# CAN-to-CAN.net
KiCad netlist of a schematic drawn in Altium Designer
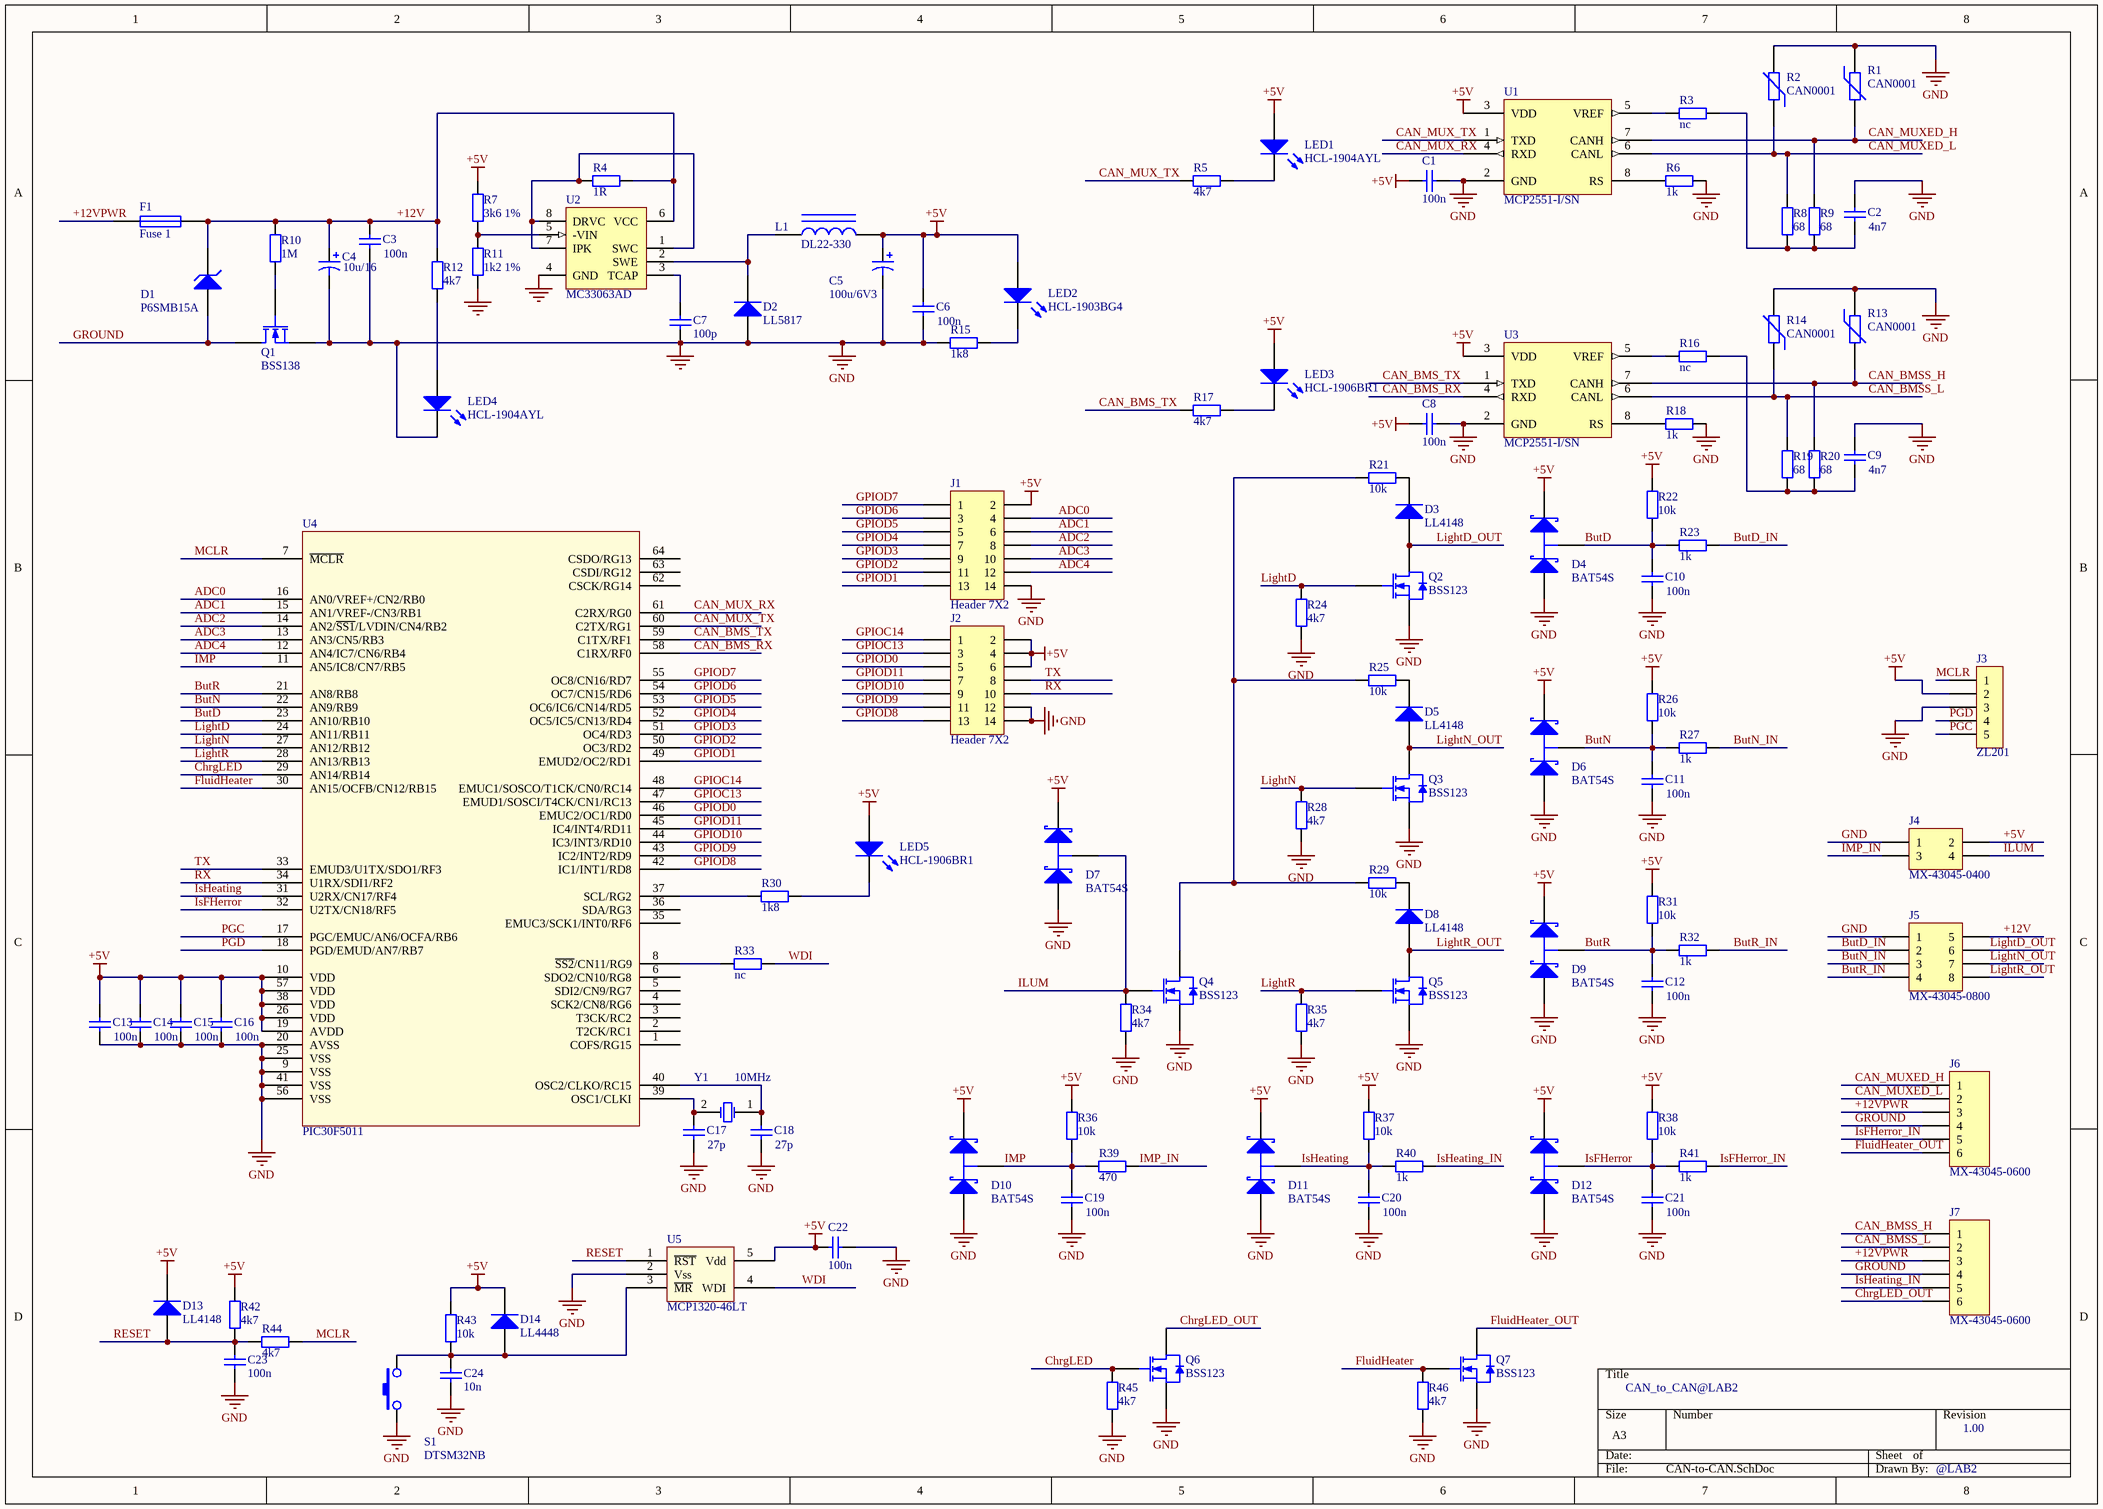
[diagram p0: CAN-to-CAN.SchDoc]

(export (version "E")
  (design (tool "Eeschema 10.0.6"))
  (components
    (comp (ref "C1")
      (value "100n")
      (footprint "0603")
      (description "Capacitor")
      (libsource (lib "Miscellaneous Devices") (part "Cap"))
    )
    (comp (ref "C2")
      (value "4n7")
      (footprint "0603")
      (description "Capacitor")
      (libsource (lib "Miscellaneous Devices") (part "Cap"))
    )
    (comp (ref "C3")
      (value "100n")
      (footprint "3.2X1.6X1.1")
      (description "Capacitor")
      (libsource (lib "Miscellaneous Devices") (part "Cap"))
    )
    (comp (ref "C4")
      (value "10u/16")
      (footprint "1608[0603]")
      (description "Polarized Capacitor (Radial)")
      (libsource (lib "Miscellaneous Devices") (part "Cap Pol1"))
    )
    (comp (ref "C5")
      (value "100u/6V3")
      (footprint "0402")
      (description "Polarized Capacitor (Radial)")
      (libsource (lib "Miscellaneous Devices") (part "Cap Pol1"))
    )
    (comp (ref "C6")
      (value "100n")
      (footprint "0603")
      (description "Capacitor")
      (libsource (lib "Miscellaneous Devices") (part "Cap"))
    )
    (comp (ref "C7")
      (value "100p")
      (footprint "0603")
      (description "Capacitor")
      (libsource (lib "Miscellaneous Devices") (part "Cap"))
    )
    (comp (ref "C8")
      (value "100n")
      (footprint "0603")
      (description "Capacitor")
      (libsource (lib "Miscellaneous Devices") (part "Cap"))
    )
    (comp (ref "C9")
      (value "4n7")
      (footprint "0603")
      (description "Capacitor")
      (libsource (lib "Miscellaneous Devices") (part "Cap"))
    )
    (comp (ref "C10")
      (value "100n")
      (footprint "0603")
      (description "Capacitor")
      (libsource (lib "Miscellaneous Devices") (part "Cap"))
    )
    (comp (ref "C11")
      (value "100n")
      (footprint "0603")
      (description "Capacitor")
      (libsource (lib "Miscellaneous Devices") (part "Cap"))
    )
    (comp (ref "C12")
      (value "100n")
      (footprint "0603")
      (description "Capacitor")
      (libsource (lib "Miscellaneous Devices") (part "Cap"))
    )
    (comp (ref "C13")
      (value "100n")
      (footprint "0603")
      (description "Capacitor")
      (libsource (lib "Miscellaneous Devices") (part "Cap"))
    )
    (comp (ref "C14")
      (value "100n")
      (footprint "0603")
      (description "Capacitor")
      (libsource (lib "Miscellaneous Devices") (part "Cap"))
    )
    (comp (ref "C15")
      (value "100n")
      (footprint "0603")
      (description "Capacitor")
      (libsource (lib "Miscellaneous Devices") (part "Cap"))
    )
    (comp (ref "C16")
      (value "100n")
      (footprint "0603")
      (description "Capacitor")
      (libsource (lib "Miscellaneous Devices") (part "Cap"))
    )
    (comp (ref "C17")
      (value "27p")
      (footprint "0603")
      (description "Capacitor")
      (libsource (lib "Miscellaneous Devices") (part "Cap"))
    )
    (comp (ref "C18")
      (value "27p")
      (footprint "0603")
      (description "Capacitor")
      (libsource (lib "Miscellaneous Devices") (part "Cap"))
    )
    (comp (ref "C19")
      (value "100n")
      (footprint "0603")
      (description "Capacitor")
      (libsource (lib "Miscellaneous Devices") (part "Cap"))
    )
    (comp (ref "C20")
      (value "100n")
      (footprint "0603")
      (description "Capacitor")
      (libsource (lib "Miscellaneous Devices") (part "Cap"))
    )
    (comp (ref "C21")
      (value "100n")
      (footprint "0603")
      (description "Capacitor")
      (libsource (lib "Miscellaneous Devices") (part "Cap"))
    )
    (comp (ref "C22")
      (value "100n")
      (footprint "0603")
      (description "Capacitor")
      (libsource (lib "Miscellaneous Devices") (part "Cap"))
    )
    (comp (ref "C23")
      (value "100n")
      (footprint "0603")
      (description "Capacitor")
      (libsource (lib "Miscellaneous Devices") (part "Cap"))
    )
    (comp (ref "C24")
      (value "10n")
      (footprint "0603")
      (description "Capacitor")
      (libsource (lib "Miscellaneous Devices") (part "Cap"))
    )
    (comp (ref "D1")
      (value "P6SMB15A")
      (footprint "SMB")
      (description "Zener Diode")
      (libsource (lib "Miscellaneous Devices") (part "D Zener"))
    )
    (comp (ref "D2")
      (value "LL5817")
      (footprint "3.2X1.6X1.1")
      (description "High Conductance Fast Diode")
      (libsource (lib "FSC Discrete Diode") (part "1N4148"))
    )
    (comp (ref "D3")
      (value "LL4148")
      (footprint "3.2X1.6X1.1")
      (description "High Conductance Fast Diode")
      (libsource (lib "FSC Discrete Diode") (part "1N4148"))
    )
    (comp (ref "D4")
      (value "BAT54S")
      (footprint "3.2X1.6X1.1")
      (description "Schottky Barrier Double Diode")
      (libsource (lib "Philips Discrete Diode - Schottky") (part "BAT54S"))
    )
    (comp (ref "D5")
      (value "LL4148")
      (footprint "3.2X1.6X1.1")
      (description "High Conductance Fast Diode")
      (libsource (lib "FSC Discrete Diode") (part "1N4148"))
    )
    (comp (ref "D6")
      (value "BAT54S")
      (footprint "3.5X2.8X1.9")
      (description "Schottky Barrier Double Diode")
      (libsource (lib "Philips Discrete Diode - Schottky") (part "BAT54S"))
    )
    (comp (ref "D7")
      (value "BAT54S")
      (footprint "3.2X1.6X1.1")
      (description "Schottky Barrier Double Diode")
      (libsource (lib "Philips Discrete Diode - Schottky") (part "BAT54S"))
    )
    (comp (ref "D8")
      (value "LL4148")
      (footprint "3.2X1.6X1.1")
      (description "High Conductance Fast Diode")
      (libsource (lib "FSC Discrete Diode") (part "1N4148"))
    )
    (comp (ref "D9")
      (value "BAT54S")
      (footprint "3.5X2.8X1.9")
      (description "Schottky Barrier Double Diode")
      (libsource (lib "Philips Discrete Diode - Schottky") (part "BAT54S"))
    )
    (comp (ref "D10")
      (value "BAT54S")
      (footprint "3.2X1.6X1.1")
      (description "Schottky Barrier Double Diode")
      (libsource (lib "Philips Discrete Diode - Schottky") (part "BAT54S"))
    )
    (comp (ref "D11")
      (value "BAT54S")
      (footprint "3.2X1.6X1.1")
      (description "Schottky Barrier Double Diode")
      (libsource (lib "Philips Discrete Diode - Schottky") (part "BAT54S"))
    )
    (comp (ref "D12")
      (value "BAT54S")
      (footprint "3.2X1.6X1.1")
      (description "Schottky Barrier Double Diode")
      (libsource (lib "Philips Discrete Diode - Schottky") (part "BAT54S"))
    )
    (comp (ref "D13")
      (value "LL4148")
      (footprint "3.2X1.6X1.1")
      (description "High Conductance Fast Diode")
      (libsource (lib "FSC Discrete Diode") (part "1N4148"))
    )
    (comp (ref "D14")
      (value "LL4448")
      (footprint "3.2X1.6X1.1")
      (description "Default Diode")
      (libsource (lib "Miscellaneous Devices") (part "Diode"))
    )
    (comp (ref "F1")
      (value "Fuse 1")
      (footprint "1812")
      (description "Fuse")
      (libsource (lib "Miscellaneous Devices") (part "Fuse 1"))
    )
    (comp (ref "J1")
      (value "Header 7X2")
      (footprint "HDR2X7")
      (description "Header, 7-Pin, Dual row")
      (libsource (lib "Miscellaneous Connectors") (part "Header 7X2"))
    )
    (comp (ref "J2")
      (value "Header 7X2")
      (footprint "HDR2X7")
      (description "Header, 7-Pin, Dual row")
      (libsource (lib "Miscellaneous Connectors") (part "Header 7X2"))
    )
    (comp (ref "J3")
      (value "ZL201")
      (footprint "HDR1X5")
      (description "Connector")
      (libsource (lib "*") (part "CON5"))
    )
    (comp (ref "J4")
      (value "MX-43045-0400")
      (footprint "MHDR2X2")
      (description "Header, 2-Pin, Dual row")
      (libsource (lib "Miscellaneous Connectors") (part "Header 2X2"))
    )
    (comp (ref "J5")
      (value "MX-43045-0800")
      (footprint "MHDR2X8")
      (description "Header, 4-Pin, Dual row")
      (libsource (lib "Miscellaneous Connectors") (part "Header 4X2A"))
    )
    (comp (ref "J6")
      (value "MX-43045-0600")
      (footprint "MHDR1X6")
      (description "Header, 6-Pin")
      (libsource (lib "Miscellaneous Connectors") (part "Header 6"))
    )
    (comp (ref "J7")
      (value "MX-43045-0600")
      (footprint "MHDR1X6")
      (description "Header, 6-Pin")
      (libsource (lib "Miscellaneous Connectors") (part "Header 6"))
    )
    (comp (ref "L1")
      (value "DL22-330")
      (footprint "14-1210")
      (description "Magnetic-Core Inductor")
      (libsource (lib "Miscellaneous Devices") (part "Inductor Iron"))
    )
    (comp (ref "LED1")
      (value "HCL-1904AYL")
      (footprint "0603")
      (description "Typical BLUE SiC LED")
      (libsource (lib "Miscellaneous Devices") (part "LED3"))
    )
    (comp (ref "LED2")
      (value "HCL-1903BG4")
      (footprint "0603")
      (description "Typical BLUE SiC LED")
      (libsource (lib "Miscellaneous Devices") (part "LED3"))
    )
    (comp (ref "LED3")
      (value "HCL-1906BR1")
      (footprint "0603")
      (description "Typical BLUE SiC LED")
      (libsource (lib "Miscellaneous Devices") (part "LED3"))
    )
    (comp (ref "LED4")
      (value "HCL-1904AYL")
      (footprint "0603")
      (description "Typical BLUE SiC LED")
      (libsource (lib "Miscellaneous Devices") (part "LED3"))
    )
    (comp (ref "LED5")
      (value "HCL-1906BR1")
      (footprint "0603")
      (description "Typical BLUE SiC LED")
      (libsource (lib "Miscellaneous Devices") (part "LED3"))
    )
    (comp (ref "Q1")
      (value "BSS138")
      (footprint "3.2X1.6X1.1")
      (description "N-Channel Enhancement Mode Vertical DMOS FET")
      (libsource (lib "Zetex Discrete MOSFET") (part "BSS138"))
    )
    (comp (ref "Q2")
      (value "BSS123")
      (footprint "3.2X1.6X1.1")
      (description "N-channel Enhancement Mode Vertical D-MOSFET")
      (libsource (lib "Philips Discrete MOSFET - Low Power") (part "BSS123"))
    )
    (comp (ref "Q3")
      (value "BSS123")
      (footprint "3.2X1.6X1.1")
      (description "N-channel Enhancement Mode Vertical D-MOSFET")
      (libsource (lib "Philips Discrete MOSFET - Low Power") (part "BSS123"))
    )
    (comp (ref "Q4")
      (value "BSS123")
      (footprint "3.5X2.8X1.9")
      (description "N-channel Enhancement Mode Vertical D-MOSFET")
      (libsource (lib "Philips Discrete MOSFET - Low Power") (part "BSS123"))
    )
    (comp (ref "Q5")
      (value "BSS123")
      (footprint "3.5X2.8X1.9")
      (description "N-channel Enhancement Mode Vertical D-MOSFET")
      (libsource (lib "Philips Discrete MOSFET - Low Power") (part "BSS123"))
    )
    (comp (ref "Q6")
      (value "BSS123")
      (footprint "3.2X1.6X1.1")
      (description "N-channel Enhancement Mode Vertical D-MOSFET")
      (libsource (lib "Philips Discrete MOSFET - Low Power") (part "BSS123"))
    )
    (comp (ref "Q7")
      (value "BSS123")
      (footprint "3.5X2.8X1.9")
      (description "N-channel Enhancement Mode Vertical D-MOSFET")
      (libsource (lib "Philips Discrete MOSFET - Low Power") (part "BSS123"))
    )
    (comp (ref "R1")
      (value "CAN0001")
      (footprint "0603")
      (description "Varistor (Voltage-Sensitive Resistor)")
      (libsource (lib "Miscellaneous Devices") (part "Res Varistor"))
    )
    (comp (ref "R2")
      (value "CAN0001")
      (footprint "0603")
      (description "Varistor (Voltage-Sensitive Resistor)")
      (libsource (lib "Miscellaneous Devices") (part "Res Varistor"))
    )
    (comp (ref "R3")
      (value "nc")
      (footprint "0603")
      (description "Resistor")
      (libsource (lib "Miscellaneous Devices") (part "Res2"))
    )
    (comp (ref "R4")
      (value "1R")
      (footprint "RESC6332")
      (description "Resistor")
      (libsource (lib "Miscellaneous Devices") (part "Res2"))
    )
    (comp (ref "R5")
      (value "4k7")
      (footprint "0603")
      (description "Resistor")
      (libsource (lib "") (part "Res2_1"))
    )
    (comp (ref "R6")
      (value "1k")
      (footprint "0603")
      (description "Resistor")
      (libsource (lib "Miscellaneous Devices") (part "Res2"))
    )
    (comp (ref "R7")
      (value "3k6 1%")
      (footprint "0603")
      (description "Resistor")
      (libsource (lib "") (part "Res2_2"))
    )
    (comp (ref "R8")
      (value "68")
      (footprint "0603")
      (description "Resistor")
      (libsource (lib "") (part "Res2_2"))
    )
    (comp (ref "R9")
      (value "68")
      (footprint "0603")
      (description "Resistor")
      (libsource (lib "") (part "Res2_2"))
    )
    (comp (ref "R10")
      (value "1M")
      (footprint "0603")
      (description "Resistor")
      (libsource (lib "") (part "Res2_2"))
    )
    (comp (ref "R11")
      (value "1k2 1%")
      (footprint "0603")
      (description "Resistor")
      (libsource (lib "") (part "Res2_3"))
    )
    (comp (ref "R12")
      (value "4k7")
      (footprint "0603")
      (description "Resistor")
      (libsource (lib "") (part "Res2_2"))
    )
    (comp (ref "R13")
      (value "CAN0001")
      (footprint "0603")
      (description "Varistor (Voltage-Sensitive Resistor)")
      (libsource (lib "Miscellaneous Devices") (part "Res Varistor"))
    )
    (comp (ref "R14")
      (value "CAN0001")
      (footprint "0603")
      (description "Varistor (Voltage-Sensitive Resistor)")
      (libsource (lib "Miscellaneous Devices") (part "Res Varistor"))
    )
    (comp (ref "R15")
      (value "1k8")
      (footprint "0603")
      (description "Resistor")
      (libsource (lib "") (part "Res2_1"))
    )
    (comp (ref "R16")
      (value "nc")
      (footprint "0603")
      (description "Resistor")
      (libsource (lib "Miscellaneous Devices") (part "Res2"))
    )
    (comp (ref "R17")
      (value "4k7")
      (footprint "0603")
      (description "Resistor")
      (libsource (lib "") (part "Res2_1"))
    )
    (comp (ref "R18")
      (value "1k")
      (footprint "0603")
      (description "Resistor")
      (libsource (lib "Miscellaneous Devices") (part "Res2"))
    )
    (comp (ref "R19")
      (value "68")
      (footprint "0603")
      (description "Resistor")
      (libsource (lib "") (part "Res2_2"))
    )
    (comp (ref "R20")
      (value "68")
      (footprint "0603")
      (description "Resistor")
      (libsource (lib "") (part "Res2_2"))
    )
    (comp (ref "R21")
      (value "10k")
      (footprint "0603")
      (description "Resistor")
      (libsource (lib "Miscellaneous Devices") (part "Res2"))
    )
    (comp (ref "R22")
      (value "10k")
      (footprint "0603")
      (description "Resistor")
      (libsource (lib "") (part "Res2_2"))
    )
    (comp (ref "R23")
      (value "1k")
      (footprint "0603")
      (description "Resistor")
      (libsource (lib "") (part "Res2_1"))
    )
    (comp (ref "R24")
      (value "4k7")
      (footprint "0603")
      (description "Resistor")
      (libsource (lib "") (part "Res2_2"))
    )
    (comp (ref "R25")
      (value "10k")
      (footprint "0603")
      (description "Resistor")
      (libsource (lib "Miscellaneous Devices") (part "Res2"))
    )
    (comp (ref "R26")
      (value "10k")
      (footprint "0603")
      (description "Resistor")
      (libsource (lib "") (part "Res2_2"))
    )
    (comp (ref "R27")
      (value "1k")
      (footprint "0603")
      (description "Resistor")
      (libsource (lib "") (part "Res2_1"))
    )
    (comp (ref "R28")
      (value "4k7")
      (footprint "0603")
      (description "Resistor")
      (libsource (lib "") (part "Res2_2"))
    )
    (comp (ref "R29")
      (value "10k")
      (footprint "0603")
      (description "Resistor")
      (libsource (lib "Miscellaneous Devices") (part "Res2"))
    )
    (comp (ref "R30")
      (value "1k8")
      (footprint "0603")
      (description "Resistor")
      (libsource (lib "") (part "Res2_1"))
    )
    (comp (ref "R31")
      (value "10k")
      (footprint "0603")
      (description "Resistor")
      (libsource (lib "") (part "Res2_2"))
    )
    (comp (ref "R32")
      (value "1k")
      (footprint "0603")
      (description "Resistor")
      (libsource (lib "") (part "Res2_1"))
    )
    (comp (ref "R33")
      (value "nc")
      (footprint "0603")
      (description "Resistor")
      (libsource (lib "") (part "Res2_1"))
    )
    (comp (ref "R34")
      (value "4k7")
      (footprint "0603")
      (description "Resistor")
      (libsource (lib "") (part "Res2_2"))
    )
    (comp (ref "R35")
      (value "4k7")
      (footprint "0603")
      (description "Resistor")
      (libsource (lib "") (part "Res2_2"))
    )
    (comp (ref "R36")
      (value "10k")
      (footprint "0603")
      (description "Resistor")
      (libsource (lib "") (part "Res2_2"))
    )
    (comp (ref "R37")
      (value "10k")
      (footprint "0603")
      (description "Resistor")
      (libsource (lib "") (part "Res2_2"))
    )
    (comp (ref "R38")
      (value "10k")
      (footprint "0603")
      (description "Resistor")
      (libsource (lib "") (part "Res2_2"))
    )
    (comp (ref "R39")
      (value "470")
      (footprint "0603")
      (description "Resistor")
      (libsource (lib "") (part "Res2_1"))
    )
    (comp (ref "R40")
      (value "1k")
      (footprint "0603")
      (description "Resistor")
      (libsource (lib "") (part "Res2_1"))
    )
    (comp (ref "R41")
      (value "1k")
      (footprint "0603")
      (description "Resistor")
      (libsource (lib "") (part "Res2_1"))
    )
    (comp (ref "R42")
      (value "4k7")
      (footprint "0603")
      (description "Resistor")
      (libsource (lib "") (part "Res2_2"))
    )
    (comp (ref "R43")
      (value "10k")
      (footprint "0603")
      (description "Resistor")
      (libsource (lib "") (part "Res2_3"))
    )
    (comp (ref "R44")
      (value "4k7")
      (footprint "0603")
      (description "Resistor")
      (libsource (lib "") (part "Res2_1"))
    )
    (comp (ref "R45")
      (value "4k7")
      (footprint "0603")
      (description "Resistor")
      (libsource (lib "") (part "Res2_2"))
    )
    (comp (ref "R46")
      (value "4k7")
      (footprint "0603")
      (description "Resistor")
      (libsource (lib "") (part "Res2_2"))
    )
    (comp (ref "S1")
      (value "DTSM32NB")
      (footprint "3.5X2.8X1.9")
      (description "Switch PushButton")
      (libsource (lib "*") (part "PUSHB"))
    )
    (comp (ref "U1")
      (value "MCP2551-I/SN")
      (footprint "HDR2X8")
      (description "High Speed CAN Transceiver, 8-Pin Plastic SOIC, Industrial Grade")
      (libsource (lib "Microchip Interface Line Transceiver") (part "MCP2551-I/SN"))
    )
    (comp (ref "U2")
      (value "MC33063AD")
      (footprint "SO8_N")
      (description "DC-to-DC Converter Control Circuit")
      (libsource (lib "Motorola Power Mgt DC-DC Converter") (part "MC33063AD"))
    )
    (comp (ref "U3")
      (value "MCP2551-I/SN")
      (footprint "MHDR1X8")
      (description "High Speed CAN Transceiver, 8-Pin Plastic SOIC, Industrial Grade")
      (libsource (lib "Microchip Interface Line Transceiver") (part "MCP2551-I/SN"))
    )
    (comp (ref "U4")
      (value "PIC30F5011")
      (footprint "QFP50P1200X1200X120-64N")
      (description "PIC30F5011 - Up")
      (libsource (lib "X-Tro's Misc") (part "PIC30F5011"))
    )
    (comp (ref "U5")
      (value "MCP1320-46LT")
      (footprint "HDR1X5")
      (libsource (lib "X-Tro's Misc") (part "MCP1320"))
    )
    (comp (ref "Y1")
      (value "10MHz")
      (footprint "3.2X1.6X1.1")
      (description "Crystal Oscillator")
      (libsource (lib "Miscellaneous Devices") (part "XTAL"))
    )
  )
  (nets
    (net (code "1") (name "+5V") (class "Default")
      (node (ref "C1") (pin "1") (pinfunction "1_1") (pintype "passive"))
      (node (ref "C13") (pin "1") (pinfunction "1_1") (pintype "passive"))
      (node (ref "C14") (pin "1") (pinfunction "1_1") (pintype "passive"))
      (node (ref "C15") (pin "1") (pinfunction "1_1") (pintype "passive"))
      (node (ref "C16") (pin "1") (pinfunction "1_1") (pintype "passive"))
      (node (ref "C22") (pin "1") (pinfunction "1_1") (pintype "passive"))
      (node (ref "C5") (pin "1") (pinfunction "1_1") (pintype "passive"))
      (node (ref "C6") (pin "1") (pinfunction "1_1") (pintype "passive"))
      (node (ref "C8") (pin "1") (pinfunction "1_1") (pintype "passive"))
      (node (ref "D10") (pin "2") (pinfunction "K_2") (pintype "passive"))
      (node (ref "D11") (pin "2") (pinfunction "K_2") (pintype "passive"))
      (node (ref "D12") (pin "2") (pinfunction "K_2") (pintype "passive"))
      (node (ref "D13") (pin "2") (pinfunction "K_2") (pintype "passive"))
      (node (ref "D14") (pin "2") (pinfunction "K_2") (pintype "passive"))
      (node (ref "D4") (pin "2") (pinfunction "K_2") (pintype "passive"))
      (node (ref "D6") (pin "2") (pinfunction "K_2") (pintype "passive"))
      (node (ref "D7") (pin "2") (pinfunction "K_2") (pintype "passive"))
      (node (ref "D9") (pin "2") (pinfunction "K_2") (pintype "passive"))
      (node (ref "J1") (pin "2") (pinfunction "2_2") (pintype "passive"))
      (node (ref "J2") (pin "2") (pinfunction "2_2") (pintype "passive"))
      (node (ref "J2") (pin "4") (pinfunction "4_4") (pintype "passive"))
      (node (ref "J2") (pin "6") (pinfunction "6_6") (pintype "passive"))
      (node (ref "J3") (pin "2") (pinfunction "2_2") (pintype "passive"))
      (node (ref "J4") (pin "2") (pinfunction "2_2") (pintype "passive"))
      (node (ref "L1") (pin "2") (pinfunction "2_2") (pintype "passive"))
      (node (ref "LED1") (pin "1") (pinfunction "A_1") (pintype "passive"))
      (node (ref "LED2") (pin "1") (pinfunction "A_1") (pintype "passive"))
      (node (ref "LED3") (pin "1") (pinfunction "A_1") (pintype "passive"))
      (node (ref "LED5") (pin "1") (pinfunction "A_1") (pintype "passive"))
      (node (ref "R22") (pin "1") (pinfunction "1_1") (pintype "passive"))
      (node (ref "R26") (pin "1") (pinfunction "1_1") (pintype "passive"))
      (node (ref "R31") (pin "1") (pinfunction "1_1") (pintype "passive"))
      (node (ref "R36") (pin "1") (pinfunction "1_1") (pintype "passive"))
      (node (ref "R37") (pin "1") (pinfunction "1_1") (pintype "passive"))
      (node (ref "R38") (pin "1") (pinfunction "1_1") (pintype "passive"))
      (node (ref "R42") (pin "1") (pinfunction "1_1") (pintype "passive"))
      (node (ref "R43") (pin "2") (pinfunction "2_2") (pintype "passive"))
      (node (ref "R7") (pin "1") (pinfunction "1_1") (pintype "passive"))
      (node (ref "U1") (pin "3") (pinfunction "VDD_3") (pintype "power_in"))
      (node (ref "U3") (pin "3") (pinfunction "VDD_3") (pintype "power_in"))
      (node (ref "U4") (pin "10") (pinfunction "VDD_10") (pintype "passive"))
      (node (ref "U4") (pin "19") (pinfunction "AVDD_19") (pintype "passive"))
      (node (ref "U4") (pin "26") (pinfunction "VDD_26") (pintype "passive"))
      (node (ref "U4") (pin "38") (pinfunction "VDD_38") (pintype "passive"))
      (node (ref "U4") (pin "57") (pinfunction "VDD_57") (pintype "passive"))
      (node (ref "U5") (pin "5") (pinfunction "Vdd_5") (pintype "passive"))
    )
    (net (code "2") (name "/+12V") (class "Default")
      (node (ref "C3") (pin "1") (pinfunction "1_1") (pintype "passive"))
      (node (ref "C4") (pin "1") (pinfunction "1_1") (pintype "passive"))
      (node (ref "D1") (pin "2") (pinfunction "K_2") (pintype "passive"))
      (node (ref "F1") (pin "2") (pinfunction "2_2") (pintype "passive"))
      (node (ref "J5") (pin "5") (pinfunction "5_5") (pintype "passive"))
      (node (ref "R10") (pin "1") (pinfunction "1_1") (pintype "passive"))
      (node (ref "R12") (pin "1") (pinfunction "1_1") (pintype "passive"))
      (node (ref "R4") (pin "2") (pinfunction "2_2") (pintype "passive"))
      (node (ref "U2") (pin "6") (pinfunction "VCC_6") (pintype "power_in"))
    )
    (net (code "3") (name "/+12VPWR") (class "Default")
      (node (ref "F1") (pin "1") (pinfunction "1_1") (pintype "passive"))
      (node (ref "J6") (pin "3") (pinfunction "3_3") (pintype "passive"))
      (node (ref "J7") (pin "3") (pinfunction "3_3") (pintype "passive"))
    )
    (net (code "4") (name "/ADC0") (class "Default")
      (node (ref "J1") (pin "4") (pinfunction "4_4") (pintype "passive"))
      (node (ref "U4") (pin "16") (pinfunction "AN0/VREF+/CN2/RB0_16") (pintype "passive"))
    )
    (net (code "5") (name "/ADC1") (class "Default")
      (node (ref "J1") (pin "6") (pinfunction "6_6") (pintype "passive"))
      (node (ref "U4") (pin "15") (pinfunction "AN1/VREF-/CN3/RB1_15") (pintype "passive"))
    )
    (net (code "6") (name "/ADC2") (class "Default")
      (node (ref "J1") (pin "8") (pinfunction "8_8") (pintype "passive"))
      (node (ref "U4") (pin "14") (pinfunction "AN2/~{SS1}/LVDIN/CN4/RB2_14") (pintype "passive"))
    )
    (net (code "7") (name "/ADC3") (class "Default")
      (node (ref "J1") (pin "10") (pinfunction "10_10") (pintype "passive"))
      (node (ref "U4") (pin "13") (pinfunction "AN3/CN5/RB3_13") (pintype "passive"))
    )
    (net (code "8") (name "/ADC4") (class "Default")
      (node (ref "J1") (pin "12") (pinfunction "12_12") (pintype "passive"))
      (node (ref "U4") (pin "12") (pinfunction "AN4/IC7/CN6/RB4_12") (pintype "passive"))
    )
    (net (code "9") (name "/ButD") (class "Default")
      (node (ref "C10") (pin "1") (pinfunction "1_1") (pintype "passive"))
      (node (ref "D4") (pin "3") (pinfunction "C_3") (pintype "passive"))
      (node (ref "R22") (pin "2") (pinfunction "2_2") (pintype "passive"))
      (node (ref "R23") (pin "2") (pinfunction "2_2") (pintype "passive"))
      (node (ref "U4") (pin "23") (pinfunction "AN10/RB10_23") (pintype "passive"))
    )
    (net (code "10") (name "/ButD_IN") (class "Default")
      (node (ref "J5") (pin "2") (pinfunction "2_2") (pintype "passive"))
      (node (ref "R23") (pin "1") (pinfunction "1_1") (pintype "passive"))
    )
    (net (code "11") (name "/ButN") (class "Default")
      (node (ref "C11") (pin "1") (pinfunction "1_1") (pintype "passive"))
      (node (ref "D6") (pin "3") (pinfunction "C_3") (pintype "passive"))
      (node (ref "R26") (pin "2") (pinfunction "2_2") (pintype "passive"))
      (node (ref "R27") (pin "2") (pinfunction "2_2") (pintype "passive"))
      (node (ref "U4") (pin "22") (pinfunction "AN9/RB9_22") (pintype "passive"))
    )
    (net (code "12") (name "/ButN_IN") (class "Default")
      (node (ref "J5") (pin "3") (pinfunction "3_3") (pintype "passive"))
      (node (ref "R27") (pin "1") (pinfunction "1_1") (pintype "passive"))
    )
    (net (code "13") (name "/ButR") (class "Default")
      (node (ref "C12") (pin "1") (pinfunction "1_1") (pintype "passive"))
      (node (ref "D9") (pin "3") (pinfunction "C_3") (pintype "passive"))
      (node (ref "R31") (pin "2") (pinfunction "2_2") (pintype "passive"))
      (node (ref "R32") (pin "2") (pinfunction "2_2") (pintype "passive"))
      (node (ref "U4") (pin "21") (pinfunction "AN8/RB8_21") (pintype "passive"))
    )
    (net (code "14") (name "/ButR_IN") (class "Default")
      (node (ref "J5") (pin "4") (pinfunction "4_4") (pintype "passive"))
      (node (ref "R32") (pin "1") (pinfunction "1_1") (pintype "passive"))
    )
    (net (code "15") (name "/CAN_BMSS_H") (class "Default")
      (node (ref "J7") (pin "1") (pinfunction "1_1") (pintype "passive"))
      (node (ref "R13") (pin "2") (pinfunction "2_2") (pintype "passive"))
      (node (ref "R20") (pin "1") (pinfunction "1_1") (pintype "passive"))
      (node (ref "U3") (pin "7") (pinfunction "CANH_7") (pintype "output"))
    )
    (net (code "16") (name "/CAN_BMSS_L") (class "Default")
      (node (ref "J7") (pin "2") (pinfunction "2_2") (pintype "passive"))
      (node (ref "R14") (pin "1") (pinfunction "1_1") (pintype "passive"))
      (node (ref "R19") (pin "1") (pinfunction "1_1") (pintype "passive"))
      (node (ref "U3") (pin "6") (pinfunction "CANL_6") (pintype "output"))
    )
    (net (code "17") (name "/CAN_BMS_RX") (class "Default")
      (node (ref "U3") (pin "4") (pinfunction "RXD_4") (pintype "output"))
      (node (ref "U4") (pin "58") (pinfunction "C1RX/RF0_58") (pintype "passive"))
    )
    (net (code "18") (name "/CAN_BMS_TX") (class "Default")
      (node (ref "R17") (pin "2") (pinfunction "2_2") (pintype "passive"))
      (node (ref "U3") (pin "1") (pinfunction "TXD_1") (pintype "input"))
      (node (ref "U4") (pin "59") (pinfunction "C1TX/RF1_59") (pintype "passive"))
    )
    (net (code "19") (name "/CAN_MUXED_H") (class "Default")
      (node (ref "J6") (pin "1") (pinfunction "1_1") (pintype "passive"))
      (node (ref "R1") (pin "2") (pinfunction "2_2") (pintype "passive"))
      (node (ref "R9") (pin "1") (pinfunction "1_1") (pintype "passive"))
      (node (ref "U1") (pin "7") (pinfunction "CANH_7") (pintype "output"))
    )
    (net (code "20") (name "/CAN_MUXED_L") (class "Default")
      (node (ref "J6") (pin "2") (pinfunction "2_2") (pintype "passive"))
      (node (ref "R2") (pin "1") (pinfunction "1_1") (pintype "passive"))
      (node (ref "R8") (pin "1") (pinfunction "1_1") (pintype "passive"))
      (node (ref "U1") (pin "6") (pinfunction "CANL_6") (pintype "output"))
    )
    (net (code "21") (name "/CAN_MUX_RX") (class "Default")
      (node (ref "U1") (pin "4") (pinfunction "RXD_4") (pintype "output"))
      (node (ref "U4") (pin "61") (pinfunction "C2RX/RG0_61") (pintype "passive"))
    )
    (net (code "22") (name "/CAN_MUX_TX") (class "Default")
      (node (ref "R5") (pin "2") (pinfunction "2_2") (pintype "passive"))
      (node (ref "U1") (pin "1") (pinfunction "TXD_1") (pintype "input"))
      (node (ref "U4") (pin "60") (pinfunction "C2TX/RG1_60") (pintype "passive"))
    )
    (net (code "23") (name "/ChrgLED") (class "Default")
      (node (ref "Q6") (pin "3") (pinfunction "G_3") (pintype "passive"))
      (node (ref "R45") (pin "1") (pinfunction "1_1") (pintype "passive"))
      (node (ref "U4") (pin "29") (pinfunction "AN14/RB14_29") (pintype "passive"))
    )
    (net (code "24") (name "/ChrgLED_OUT") (class "Default")
      (node (ref "J7") (pin "6") (pinfunction "6_6") (pintype "passive"))
      (node (ref "Q6") (pin "1") (pinfunction "D_1") (pintype "passive"))
    )
    (net (code "25") (name "/FluidHeater") (class "Default")
      (node (ref "Q7") (pin "3") (pinfunction "G_3") (pintype "passive"))
      (node (ref "R46") (pin "1") (pinfunction "1_1") (pintype "passive"))
      (node (ref "U4") (pin "30") (pinfunction "AN15/OCFB/CN12/RB15_30") (pintype "passive"))
    )
    (net (code "26") (name "/FluidHeater_OUT") (class "Default")
      (node (ref "J6") (pin "6") (pinfunction "6_6") (pintype "passive"))
      (node (ref "Q7") (pin "1") (pinfunction "D_1") (pintype "passive"))
    )
    (net (code "27") (name "/GPIOC13") (class "Default")
      (node (ref "J2") (pin "3") (pinfunction "3_3") (pintype "passive"))
      (node (ref "U4") (pin "47") (pinfunction "EMUD1/SOSCI/T4CK/CN1/RC13_47") (pintype "passive"))
    )
    (net (code "28") (name "/GPIOC14") (class "Default")
      (node (ref "J2") (pin "1") (pinfunction "1_1") (pintype "passive"))
      (node (ref "U4") (pin "48") (pinfunction "EMUC1/SOSCO/T1CK/CN0/RC14_48") (pintype "passive"))
    )
    (net (code "29") (name "/GPIOD0") (class "Default")
      (node (ref "J2") (pin "5") (pinfunction "5_5") (pintype "passive"))
      (node (ref "U4") (pin "46") (pinfunction "EMUC2/OC1/RD0_46") (pintype "passive"))
    )
    (net (code "30") (name "/GPIOD1") (class "Default")
      (node (ref "J1") (pin "13") (pinfunction "13_13") (pintype "passive"))
      (node (ref "U4") (pin "49") (pinfunction "EMUD2/OC2/RD1_49") (pintype "passive"))
    )
    (net (code "31") (name "/GPIOD2") (class "Default")
      (node (ref "J1") (pin "11") (pinfunction "11_11") (pintype "passive"))
      (node (ref "U4") (pin "50") (pinfunction "OC3/RD2_50") (pintype "passive"))
    )
    (net (code "32") (name "/GPIOD3") (class "Default")
      (node (ref "J1") (pin "9") (pinfunction "9_9") (pintype "passive"))
      (node (ref "U4") (pin "51") (pinfunction "OC4/RD3_51") (pintype "passive"))
    )
    (net (code "33") (name "/GPIOD4") (class "Default")
      (node (ref "J1") (pin "7") (pinfunction "7_7") (pintype "passive"))
      (node (ref "U4") (pin "52") (pinfunction "OC5/IC5/CN13/RD4_52") (pintype "passive"))
    )
    (net (code "34") (name "/GPIOD5") (class "Default")
      (node (ref "J1") (pin "5") (pinfunction "5_5") (pintype "passive"))
      (node (ref "U4") (pin "53") (pinfunction "OC6/IC6/CN14/RD5_53") (pintype "passive"))
    )
    (net (code "35") (name "/GPIOD6") (class "Default")
      (node (ref "J1") (pin "3") (pinfunction "3_3") (pintype "passive"))
      (node (ref "U4") (pin "54") (pinfunction "OC7/CN15/RD6_54") (pintype "passive"))
    )
    (net (code "36") (name "/GPIOD7") (class "Default")
      (node (ref "J1") (pin "1") (pinfunction "1_1") (pintype "passive"))
      (node (ref "U4") (pin "55") (pinfunction "OC8/CN16/RD7_55") (pintype "passive"))
    )
    (net (code "37") (name "/GPIOD8") (class "Default")
      (node (ref "J2") (pin "13") (pinfunction "13_13") (pintype "passive"))
      (node (ref "U4") (pin "42") (pinfunction "IC1/INT1/RD8_42") (pintype "passive"))
    )
    (net (code "38") (name "/GPIOD9") (class "Default")
      (node (ref "J2") (pin "11") (pinfunction "11_11") (pintype "passive"))
      (node (ref "U4") (pin "43") (pinfunction "IC2/INT2/RD9_43") (pintype "passive"))
    )
    (net (code "39") (name "/GPIOD10") (class "Default")
      (node (ref "J2") (pin "9") (pinfunction "9_9") (pintype "passive"))
      (node (ref "U4") (pin "44") (pinfunction "IC3/INT3/RD10_44") (pintype "passive"))
    )
    (net (code "40") (name "/GPIOD11") (class "Default")
      (node (ref "J2") (pin "7") (pinfunction "7_7") (pintype "passive"))
      (node (ref "U4") (pin "45") (pinfunction "IC4/INT4/RD11_45") (pintype "passive"))
    )
    (net (code "41") (name "/GROUND") (class "Default")
      (node (ref "D1") (pin "1") (pinfunction "A_1") (pintype "passive"))
      (node (ref "J6") (pin "4") (pinfunction "4_4") (pintype "passive"))
      (node (ref "J7") (pin "4") (pinfunction "4_4") (pintype "passive"))
      (node (ref "Q1") (pin "1") (pinfunction "D_1") (pintype "passive"))
    )
    (net (code "42") (name "/ILUM") (class "Default")
      (node (ref "D7") (pin "3") (pinfunction "C_3") (pintype "passive"))
      (node (ref "J4") (pin "4") (pinfunction "4_4") (pintype "passive"))
      (node (ref "Q4") (pin "3") (pinfunction "G_3") (pintype "passive"))
      (node (ref "R34") (pin "1") (pinfunction "1_1") (pintype "passive"))
    )
    (net (code "43") (name "/IMP") (class "Default")
      (node (ref "C19") (pin "1") (pinfunction "1_1") (pintype "passive"))
      (node (ref "D10") (pin "3") (pinfunction "C_3") (pintype "passive"))
      (node (ref "R36") (pin "2") (pinfunction "2_2") (pintype "passive"))
      (node (ref "R39") (pin "2") (pinfunction "2_2") (pintype "passive"))
      (node (ref "U4") (pin "11") (pinfunction "AN5/IC8/CN7/RB5_11") (pintype "passive"))
    )
    (net (code "44") (name "/IMP_IN") (class "Default")
      (node (ref "J4") (pin "3") (pinfunction "3_3") (pintype "passive"))
      (node (ref "R39") (pin "1") (pinfunction "1_1") (pintype "passive"))
    )
    (net (code "45") (name "/IsFHerror") (class "Default")
      (node (ref "C21") (pin "1") (pinfunction "1_1") (pintype "passive"))
      (node (ref "D12") (pin "3") (pinfunction "C_3") (pintype "passive"))
      (node (ref "R38") (pin "2") (pinfunction "2_2") (pintype "passive"))
      (node (ref "R41") (pin "2") (pinfunction "2_2") (pintype "passive"))
      (node (ref "U4") (pin "32") (pinfunction "U2TX/CN18/RF5_32") (pintype "passive"))
    )
    (net (code "46") (name "/IsFHerror_IN") (class "Default")
      (node (ref "J6") (pin "5") (pinfunction "5_5") (pintype "passive"))
      (node (ref "R41") (pin "1") (pinfunction "1_1") (pintype "passive"))
    )
    (net (code "47") (name "/IsHeating") (class "Default")
      (node (ref "C20") (pin "1") (pinfunction "1_1") (pintype "passive"))
      (node (ref "D11") (pin "3") (pinfunction "C_3") (pintype "passive"))
      (node (ref "R37") (pin "2") (pinfunction "2_2") (pintype "passive"))
      (node (ref "R40") (pin "2") (pinfunction "2_2") (pintype "passive"))
      (node (ref "U4") (pin "31") (pinfunction "U2RX/CN17/RF4_31") (pintype "passive"))
    )
    (net (code "48") (name "/IsHeating_IN") (class "Default")
      (node (ref "J7") (pin "5") (pinfunction "5_5") (pintype "passive"))
      (node (ref "R40") (pin "1") (pinfunction "1_1") (pintype "passive"))
    )
    (net (code "49") (name "/LightD") (class "Default")
      (node (ref "Q2") (pin "3") (pinfunction "G_3") (pintype "passive"))
      (node (ref "R24") (pin "1") (pinfunction "1_1") (pintype "passive"))
      (node (ref "U4") (pin "24") (pinfunction "AN11/RB11_24") (pintype "passive"))
    )
    (net (code "50") (name "/LightD_OUT") (class "Default")
      (node (ref "D3") (pin "1") (pinfunction "A_1") (pintype "passive"))
      (node (ref "J5") (pin "6") (pinfunction "6_6") (pintype "passive"))
      (node (ref "Q2") (pin "1") (pinfunction "D_1") (pintype "passive"))
    )
    (net (code "51") (name "/LightN") (class "Default")
      (node (ref "Q3") (pin "3") (pinfunction "G_3") (pintype "passive"))
      (node (ref "R28") (pin "1") (pinfunction "1_1") (pintype "passive"))
      (node (ref "U4") (pin "27") (pinfunction "AN12/RB12_27") (pintype "passive"))
    )
    (net (code "52") (name "/LightN_OUT") (class "Default")
      (node (ref "D5") (pin "1") (pinfunction "A_1") (pintype "passive"))
      (node (ref "J5") (pin "7") (pinfunction "7_7") (pintype "passive"))
      (node (ref "Q3") (pin "1") (pinfunction "D_1") (pintype "passive"))
    )
    (net (code "53") (name "/LightR") (class "Default")
      (node (ref "Q5") (pin "3") (pinfunction "G_3") (pintype "passive"))
      (node (ref "R35") (pin "1") (pinfunction "1_1") (pintype "passive"))
      (node (ref "U4") (pin "28") (pinfunction "AN13/RB13_28") (pintype "passive"))
    )
    (net (code "54") (name "/LightR_OUT") (class "Default")
      (node (ref "D8") (pin "1") (pinfunction "A_1") (pintype "passive"))
      (node (ref "J5") (pin "8") (pinfunction "8_8") (pintype "passive"))
      (node (ref "Q5") (pin "1") (pinfunction "D_1") (pintype "passive"))
    )
    (net (code "55") (name "/MCLR") (class "Default")
      (node (ref "J3") (pin "1") (pinfunction "1_1") (pintype "passive"))
      (node (ref "R44") (pin "1") (pinfunction "1_1") (pintype "passive"))
      (node (ref "U4") (pin "7") (pinfunction "~{MCLR}_7") (pintype "passive"))
    )
    (net (code "56") (name "/PGC") (class "Default")
      (node (ref "J3") (pin "5") (pinfunction "5_5") (pintype "passive"))
      (node (ref "U4") (pin "17") (pinfunction "PGC/EMUC/AN6/OCFA/RB6_17") (pintype "passive"))
    )
    (net (code "57") (name "/PGD") (class "Default")
      (node (ref "J3") (pin "4") (pinfunction "4_4") (pintype "passive"))
      (node (ref "U4") (pin "18") (pinfunction "PGD/EMUD/AN7/RB7_18") (pintype "passive"))
    )
    (net (code "58") (name "/RESET") (class "Default")
      (node (ref "C23") (pin "2") (pinfunction "2_2") (pintype "passive"))
      (node (ref "D13") (pin "1") (pinfunction "A_1") (pintype "passive"))
      (node (ref "R42") (pin "2") (pinfunction "2_2") (pintype "passive"))
      (node (ref "R44") (pin "2") (pinfunction "2_2") (pintype "passive"))
      (node (ref "U5") (pin "1") (pinfunction "~{RST}_1") (pintype "passive"))
    )
    (net (code "59") (name "/RX") (class "Default")
      (node (ref "J2") (pin "10") (pinfunction "10_10") (pintype "passive"))
      (node (ref "U4") (pin "34") (pinfunction "U1RX/SDI1/RF2_34") (pintype "passive"))
    )
    (net (code "60") (name "/TX") (class "Default")
      (node (ref "J2") (pin "8") (pinfunction "8_8") (pintype "passive"))
      (node (ref "U4") (pin "33") (pinfunction "EMUD3/U1TX/SDO1/RF3_33") (pintype "passive"))
    )
    (net (code "61") (name "/WDI") (class "Default")
      (node (ref "R33") (pin "1") (pinfunction "1_1") (pintype "passive"))
      (node (ref "U5") (pin "4") (pinfunction "WDI_4") (pintype "passive"))
    )
    (net (code "62") (name "GND") (class "Default")
      (node (ref "C1") (pin "2") (pinfunction "2_2") (pintype "passive"))
      (node (ref "C10") (pin "2") (pinfunction "2_2") (pintype "passive"))
      (node (ref "C11") (pin "2") (pinfunction "2_2") (pintype "passive"))
      (node (ref "C12") (pin "2") (pinfunction "2_2") (pintype "passive"))
      (node (ref "C13") (pin "2") (pinfunction "2_2") (pintype "passive"))
      (node (ref "C14") (pin "2") (pinfunction "2_2") (pintype "passive"))
      (node (ref "C15") (pin "2") (pinfunction "2_2") (pintype "passive"))
      (node (ref "C16") (pin "2") (pinfunction "2_2") (pintype "passive"))
      (node (ref "C17") (pin "2") (pinfunction "2_2") (pintype "passive"))
      (node (ref "C18") (pin "2") (pinfunction "2_2") (pintype "passive"))
      (node (ref "C19") (pin "2") (pinfunction "2_2") (pintype "passive"))
      (node (ref "C2") (pin "1") (pinfunction "1_1") (pintype "passive"))
      (node (ref "C20") (pin "2") (pinfunction "2_2") (pintype "passive"))
      (node (ref "C21") (pin "2") (pinfunction "2_2") (pintype "passive"))
      (node (ref "C22") (pin "2") (pinfunction "2_2") (pintype "passive"))
      (node (ref "C23") (pin "1") (pinfunction "1_1") (pintype "passive"))
      (node (ref "C24") (pin "1") (pinfunction "1_1") (pintype "passive"))
      (node (ref "C3") (pin "2") (pinfunction "2_2") (pintype "passive"))
      (node (ref "C4") (pin "2") (pinfunction "2_2") (pintype "passive"))
      (node (ref "C5") (pin "2") (pinfunction "2_2") (pintype "passive"))
      (node (ref "C6") (pin "2") (pinfunction "2_2") (pintype "passive"))
      (node (ref "C7") (pin "1") (pinfunction "1_1") (pintype "passive"))
      (node (ref "C8") (pin "2") (pinfunction "2_2") (pintype "passive"))
      (node (ref "C9") (pin "1") (pinfunction "1_1") (pintype "passive"))
      (node (ref "D10") (pin "1") (pinfunction "A_1") (pintype "passive"))
      (node (ref "D11") (pin "1") (pinfunction "A_1") (pintype "passive"))
      (node (ref "D12") (pin "1") (pinfunction "A_1") (pintype "passive"))
      (node (ref "D2") (pin "1") (pinfunction "A_1") (pintype "passive"))
      (node (ref "D4") (pin "1") (pinfunction "A_1") (pintype "passive"))
      (node (ref "D6") (pin "1") (pinfunction "A_1") (pintype "passive"))
      (node (ref "D7") (pin "1") (pinfunction "A_1") (pintype "passive"))
      (node (ref "D9") (pin "1") (pinfunction "A_1") (pintype "passive"))
      (node (ref "J1") (pin "14") (pinfunction "14_14") (pintype "passive"))
      (node (ref "J2") (pin "12") (pinfunction "12_12") (pintype "passive"))
      (node (ref "J2") (pin "14") (pinfunction "14_14") (pintype "passive"))
      (node (ref "J3") (pin "3") (pinfunction "3_3") (pintype "passive"))
      (node (ref "J4") (pin "1") (pinfunction "1_1") (pintype "passive"))
      (node (ref "J5") (pin "1") (pinfunction "1_1") (pintype "passive"))
      (node (ref "LED4") (pin "2") (pinfunction "K_2") (pintype "passive"))
      (node (ref "Q1") (pin "2") (pinfunction "S_2") (pintype "passive"))
      (node (ref "Q2") (pin "2") (pinfunction "S_2") (pintype "passive"))
      (node (ref "Q3") (pin "2") (pinfunction "S_2") (pintype "passive"))
      (node (ref "Q4") (pin "2") (pinfunction "S_2") (pintype "passive"))
      (node (ref "Q5") (pin "2") (pinfunction "S_2") (pintype "passive"))
      (node (ref "Q6") (pin "2") (pinfunction "S_2") (pintype "passive"))
      (node (ref "Q7") (pin "2") (pinfunction "S_2") (pintype "passive"))
      (node (ref "R1") (pin "1") (pinfunction "1_1") (pintype "passive"))
      (node (ref "R11") (pin "1") (pinfunction "1_1") (pintype "passive"))
      (node (ref "R13") (pin "1") (pinfunction "1_1") (pintype "passive"))
      (node (ref "R14") (pin "2") (pinfunction "2_2") (pintype "passive"))
      (node (ref "R15") (pin "2") (pinfunction "2_2") (pintype "passive"))
      (node (ref "R18") (pin "2") (pinfunction "2_2") (pintype "passive"))
      (node (ref "R2") (pin "2") (pinfunction "2_2") (pintype "passive"))
      (node (ref "R24") (pin "2") (pinfunction "2_2") (pintype "passive"))
      (node (ref "R28") (pin "2") (pinfunction "2_2") (pintype "passive"))
      (node (ref "R34") (pin "2") (pinfunction "2_2") (pintype "passive"))
      (node (ref "R35") (pin "2") (pinfunction "2_2") (pintype "passive"))
      (node (ref "R45") (pin "2") (pinfunction "2_2") (pintype "passive"))
      (node (ref "R46") (pin "2") (pinfunction "2_2") (pintype "passive"))
      (node (ref "R6") (pin "2") (pinfunction "2_2") (pintype "passive"))
      (node (ref "S1") (pin "1") (pintype "passive"))
      (node (ref "U1") (pin "2") (pinfunction "GND_2") (pintype "power_in"))
      (node (ref "U2") (pin "4") (pinfunction "GND_4") (pintype "power_in"))
      (node (ref "U3") (pin "2") (pinfunction "GND_2") (pintype "power_in"))
      (node (ref "U4") (pin "20") (pinfunction "AVSS_20") (pintype "passive"))
      (node (ref "U4") (pin "25") (pinfunction "VSS_25") (pintype "passive"))
      (node (ref "U4") (pin "41") (pinfunction "VSS_41") (pintype "passive"))
      (node (ref "U4") (pin "56") (pinfunction "VSS_56") (pintype "passive"))
      (node (ref "U4") (pin "9") (pinfunction "VSS_9") (pintype "passive"))
      (node (ref "U5") (pin "2") (pinfunction "Vss_2") (pintype "passive"))
    )
    (net (code "63") (name "Net-(C2-Pad2)") (class "Default")
      (node (ref "C2") (pin "2") (pinfunction "2_2") (pintype "passive"))
      (node (ref "R3") (pin "2") (pinfunction "2_2") (pintype "passive"))
      (node (ref "R8") (pin "2") (pinfunction "2_2") (pintype "passive"))
      (node (ref "R9") (pin "2") (pinfunction "2_2") (pintype "passive"))
    )
    (net (code "64") (name "Net-(C9-Pad2)") (class "Default")
      (node (ref "C9") (pin "2") (pinfunction "2_2") (pintype "passive"))
      (node (ref "R16") (pin "2") (pinfunction "2_2") (pintype "passive"))
      (node (ref "R19") (pin "2") (pinfunction "2_2") (pintype "passive"))
      (node (ref "R20") (pin "2") (pinfunction "2_2") (pintype "passive"))
    )
    (net (code "65") (name "Net-(D2-K)") (class "Default")
      (node (ref "D2") (pin "2") (pinfunction "K_2") (pintype "passive"))
      (node (ref "L1") (pin "1") (pinfunction "1_1") (pintype "passive"))
      (node (ref "U2") (pin "2") (pinfunction "SWE_2") (pintype "open_emitter"))
    )
    (net (code "66") (name "Net-(D3-K)") (class "Default")
      (node (ref "D3") (pin "2") (pinfunction "K_2") (pintype "passive"))
      (node (ref "R21") (pin "2") (pinfunction "2_2") (pintype "passive"))
    )
    (net (code "67") (name "Net-(D5-K)") (class "Default")
      (node (ref "D5") (pin "2") (pinfunction "K_2") (pintype "passive"))
      (node (ref "R25") (pin "2") (pinfunction "2_2") (pintype "passive"))
    )
    (net (code "68") (name "Net-(D8-K)") (class "Default")
      (node (ref "D8") (pin "2") (pinfunction "K_2") (pintype "passive"))
      (node (ref "R29") (pin "2") (pinfunction "2_2") (pintype "passive"))
    )
    (net (code "69") (name "Net-(D14-A)") (class "Default")
      (node (ref "C24") (pin "2") (pinfunction "2_2") (pintype "passive"))
      (node (ref "D14") (pin "1") (pinfunction "A_1") (pintype "passive"))
      (node (ref "R43") (pin "1") (pinfunction "1_1") (pintype "passive"))
      (node (ref "S1") (pin "2") (pintype "passive"))
      (node (ref "U5") (pin "3") (pinfunction "~{MR}_3") (pintype "passive"))
    )
    (net (code "70") (name "Net-(LED1-K)") (class "Default")
      (node (ref "LED1") (pin "2") (pinfunction "K_2") (pintype "passive"))
      (node (ref "R5") (pin "1") (pinfunction "1_1") (pintype "passive"))
    )
    (net (code "71") (name "Net-(LED2-K)") (class "Default")
      (node (ref "LED2") (pin "2") (pinfunction "K_2") (pintype "passive"))
      (node (ref "R15") (pin "1") (pinfunction "1_1") (pintype "passive"))
    )
    (net (code "72") (name "Net-(LED3-K)") (class "Default")
      (node (ref "LED3") (pin "2") (pinfunction "K_2") (pintype "passive"))
      (node (ref "R17") (pin "1") (pinfunction "1_1") (pintype "passive"))
    )
    (net (code "73") (name "Net-(LED4-A)") (class "Default")
      (node (ref "LED4") (pin "1") (pinfunction "A_1") (pintype "passive"))
      (node (ref "R12") (pin "2") (pinfunction "2_2") (pintype "passive"))
    )
    (net (code "74") (name "Net-(LED5-K)") (class "Default")
      (node (ref "LED5") (pin "2") (pinfunction "K_2") (pintype "passive"))
      (node (ref "R30") (pin "1") (pinfunction "1_1") (pintype "passive"))
    )
    (net (code "75") (name "Net-(Q1-G)") (class "Default")
      (node (ref "Q1") (pin "3") (pinfunction "G_3") (pintype "passive"))
      (node (ref "R10") (pin "2") (pinfunction "2_2") (pintype "passive"))
    )
    (net (code "76") (name "Net-(Q4-D)") (class "Default")
      (node (ref "Q4") (pin "1") (pinfunction "D_1") (pintype "passive"))
      (node (ref "R21") (pin "1") (pinfunction "1_1") (pintype "passive"))
      (node (ref "R25") (pin "1") (pinfunction "1_1") (pintype "passive"))
      (node (ref "R29") (pin "1") (pinfunction "1_1") (pintype "passive"))
    )
    (net (code "77") (name "Net-(U1-RS)") (class "Default")
      (node (ref "R6") (pin "1") (pinfunction "1_1") (pintype "passive"))
      (node (ref "U1") (pin "8") (pinfunction "RS_8") (pintype "passive"))
    )
    (net (code "78") (name "Net-(U1-VREF)") (class "Default")
      (node (ref "R3") (pin "1") (pinfunction "1_1") (pintype "passive"))
      (node (ref "U1") (pin "5") (pinfunction "VREF_5") (pintype "output"))
    )
    (net (code "79") (name "Net-(U2--VIN)") (class "Default")
      (node (ref "R11") (pin "2") (pinfunction "2_2") (pintype "passive"))
      (node (ref "R7") (pin "2") (pinfunction "2_2") (pintype "passive"))
      (node (ref "U2") (pin "5") (pinfunction "-VIN_5") (pintype "input"))
    )
    (net (code "80") (name "Net-(U2-DRVC)") (class "Default")
      (node (ref "R4") (pin "1") (pinfunction "1_1") (pintype "passive"))
      (node (ref "U2") (pin "1") (pinfunction "SWC_1") (pintype "open_collector"))
      (node (ref "U2") (pin "7") (pinfunction "IPK_7") (pintype "passive"))
      (node (ref "U2") (pin "8") (pinfunction "DRVC_8") (pintype "open_collector"))
    )
    (net (code "81") (name "Net-(U2-TCAP)") (class "Default")
      (node (ref "C7") (pin "2") (pinfunction "2_2") (pintype "passive"))
      (node (ref "U2") (pin "3") (pinfunction "TCAP_3") (pintype "passive"))
    )
    (net (code "82") (name "Net-(U3-RS)") (class "Default")
      (node (ref "R18") (pin "1") (pinfunction "1_1") (pintype "passive"))
      (node (ref "U3") (pin "8") (pinfunction "RS_8") (pintype "passive"))
    )
    (net (code "83") (name "Net-(U3-VREF)") (class "Default")
      (node (ref "R16") (pin "1") (pinfunction "1_1") (pintype "passive"))
      (node (ref "U3") (pin "5") (pinfunction "VREF_5") (pintype "output"))
    )
    (net (code "84") (name "Net-(U4-OSC1{slash}CLKI)") (class "Default")
      (node (ref "C17") (pin "1") (pinfunction "1_1") (pintype "passive"))
      (node (ref "U4") (pin "39") (pinfunction "OSC1/CLKI_39") (pintype "passive"))
      (node (ref "Y1") (pin "2") (pinfunction "OSC2_2") (pintype "passive"))
    )
    (net (code "85") (name "Net-(U4-OSC2{slash}CLKO{slash}RC15)") (class "Default")
      (node (ref "C18") (pin "1") (pinfunction "1_1") (pintype "passive"))
      (node (ref "U4") (pin "40") (pinfunction "OSC2/CLKO/RC15_40") (pintype "passive"))
      (node (ref "Y1") (pin "1") (pinfunction "OSC1_1") (pintype "passive"))
    )
    (net (code "86") (name "Net-(U4-SCL{slash}RG2)") (class "Default")
      (node (ref "R30") (pin "2") (pinfunction "2_2") (pintype "passive"))
      (node (ref "U4") (pin "37") (pinfunction "SCL/RG2_37") (pintype "passive"))
    )
    (net (code "87") (name "Net-(U4-~{SS2}{slash}CN11{slash}RG9)") (class "Default")
      (node (ref "R33") (pin "2") (pinfunction "2_2") (pintype "passive"))
      (node (ref "U4") (pin "8") (pinfunction "~{SS2}/CN11/RG9_8") (pintype "passive"))
    )
    (net (code "88") (name "unconnected-(U4-COFS{slash}RG15-Pad1)") (class "Default")
      (node (ref "U4") (pin "1") (pinfunction "COFS/RG15_1") (pintype "passive"))
    )
    (net (code "89") (name "unconnected-(U4-CSCK{slash}RG14-Pad62)") (class "Default")
      (node (ref "U4") (pin "62") (pinfunction "CSCK/RG14_62") (pintype "passive"))
    )
    (net (code "90") (name "unconnected-(U4-CSDI{slash}RG12-Pad63)") (class "Default")
      (node (ref "U4") (pin "63") (pinfunction "CSDI/RG12_63") (pintype "passive"))
    )
    (net (code "91") (name "unconnected-(U4-CSDO{slash}RG13-Pad64)") (class "Default")
      (node (ref "U4") (pin "64") (pinfunction "CSDO/RG13_64") (pintype "passive"))
    )
    (net (code "92") (name "unconnected-(U4-EMUC3{slash}SCK1{slash}INT0{slash}RF6-Pad35)") (class "Default")
      (node (ref "U4") (pin "35") (pinfunction "EMUC3/SCK1/INT0/RF6_35") (pintype "passive"))
    )
    (net (code "93") (name "unconnected-(U4-SCK2{slash}CN8{slash}RG6-Pad4)") (class "Default")
      (node (ref "U4") (pin "4") (pinfunction "SCK2/CN8/RG6_4") (pintype "passive"))
    )
    (net (code "94") (name "unconnected-(U4-SDA{slash}RG3-Pad36)") (class "Default")
      (node (ref "U4") (pin "36") (pinfunction "SDA/RG3_36") (pintype "passive"))
    )
    (net (code "95") (name "unconnected-(U4-SDI2{slash}CN9{slash}RG7-Pad5)") (class "Default")
      (node (ref "U4") (pin "5") (pinfunction "SDI2/CN9/RG7_5") (pintype "passive"))
    )
    (net (code "96") (name "unconnected-(U4-SDO2{slash}CN10{slash}RG8-Pad6)") (class "Default")
      (node (ref "U4") (pin "6") (pinfunction "SDO2/CN10/RG8_6") (pintype "passive"))
    )
    (net (code "97") (name "unconnected-(U4-T2CK{slash}RC1-Pad2)") (class "Default")
      (node (ref "U4") (pin "2") (pinfunction "T2CK/RC1_2") (pintype "passive"))
    )
    (net (code "98") (name "unconnected-(U4-T3CK{slash}RC2-Pad3)") (class "Default")
      (node (ref "U4") (pin "3") (pinfunction "T3CK/RC2_3") (pintype "passive"))
    )
  )
)
